# design.net
KiCad netlist of a schematic drawn in EAGLE
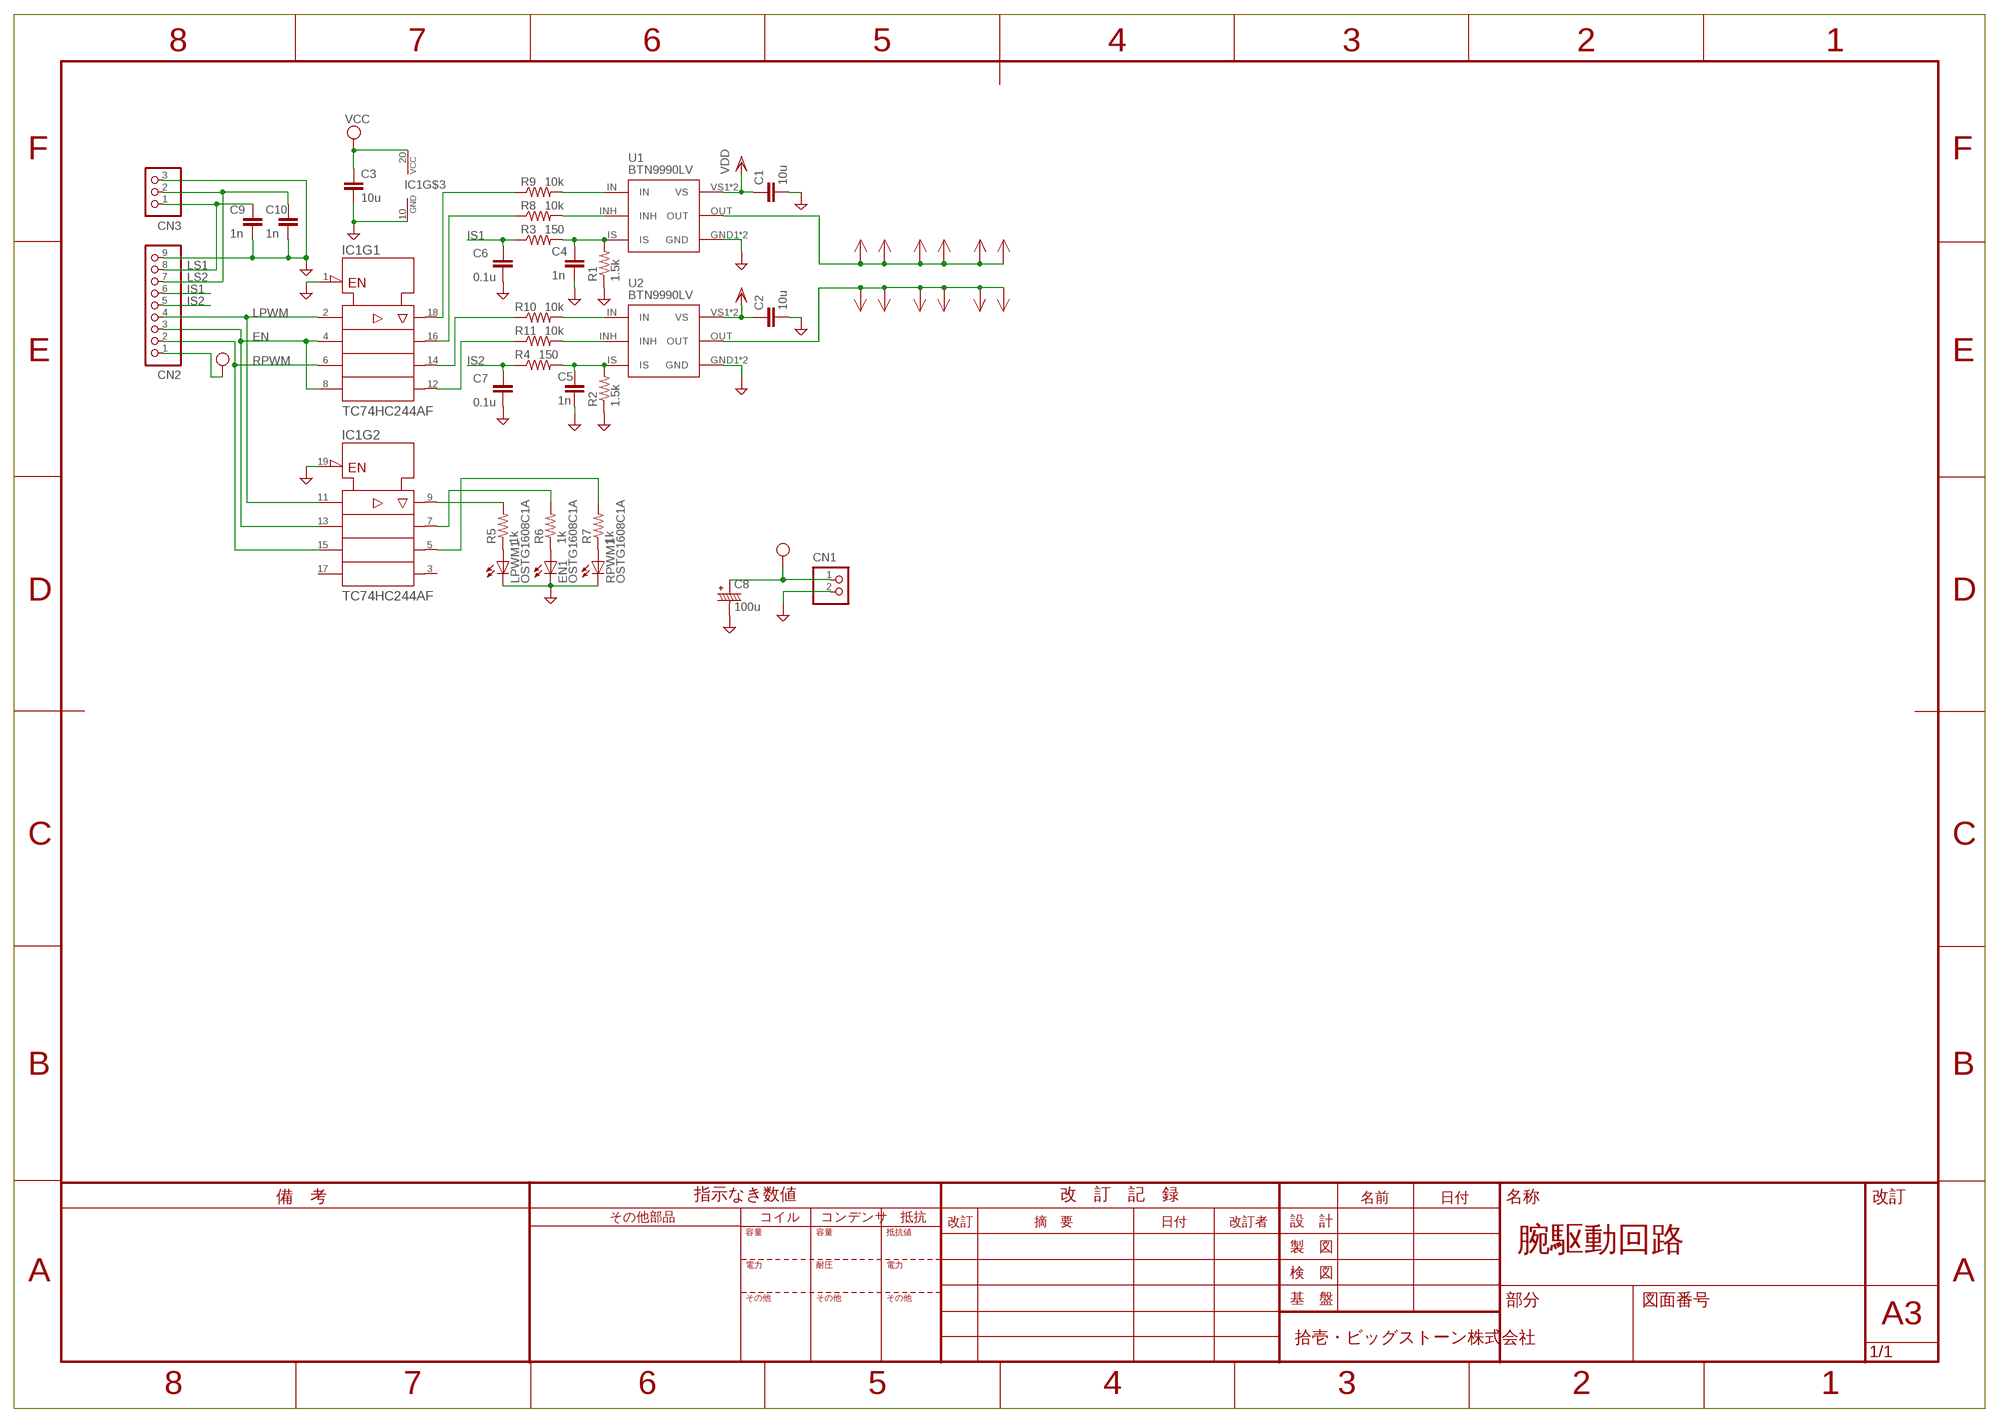
[diagram p0: schematic, sheet 1]

(export (version "E")
  (design (tool "Eeschema 10.0.6"))
  (components
    (comp (ref "C1")
      (value "10u")
      (footprint "eagle-import:C3216")
      (libsource (lib "eagle-import") (part "GCM?31CD71H106KE36K"))
    )
    (comp (ref "C2")
      (value "10u")
      (footprint "eagle-import:C3216")
      (libsource (lib "eagle-import") (part "GCM?31CD71H106KE36K"))
    )
    (comp (ref "C3")
      (value "10u")
      (footprint "eagle-import:C3216")
      (libsource (lib "eagle-import") (part "GCM?31CD71H106KE36K"))
    )
    (comp (ref "C4")
      (value "1n")
      (footprint "eagle-import:C1608")
      (libsource (lib "eagle-import") (part "GCM?188R91H102KA37D"))
    )
    (comp (ref "C5")
      (value "1n")
      (footprint "eagle-import:C1608")
      (libsource (lib "eagle-import") (part "GCM?188R91H102KA37D"))
    )
    (comp (ref "C6")
      (value "0.1u")
      (footprint "eagle-import:C1608")
      (libsource (lib "eagle-import") (part "GCM?188L81H104KA57D"))
    )
    (comp (ref "C7")
      (value "0.1u")
      (footprint "eagle-import:C1608")
      (libsource (lib "eagle-import") (part "GCM?188L81H104KA57D"))
    )
    (comp (ref "C8")
      (value "100u")
      (footprint "eagle-import:CPOL6.3-7_2.5")
      (libsource (lib "eagle-import") (part "16MH7100MEFC6.3X7"))
    )
    (comp (ref "C9")
      (value "1n")
      (footprint "eagle-import:C1608")
      (libsource (lib "eagle-import") (part "GCM?188R91H102KA37D"))
    )
    (comp (ref "C10")
      (value "1n")
      (footprint "eagle-import:C1608")
      (libsource (lib "eagle-import") (part "GCM?188R91H102KA37D"))
    )
    (comp (ref "CN1")
      (value "B2B-XH-A")
      (footprint "eagle-import:B2B-XH-A")
      (libsource (lib "eagle-import") (part "B2B-XH-A"))
    )
    (comp (ref "CN2")
      (value "B9B-XH-A")
      (footprint "eagle-import:B9B-XH-A")
      (libsource (lib "eagle-import") (part "B9B-XH-A"))
    )
    (comp (ref "CN3")
      (value "B3B-XH-A")
      (footprint "eagle-import:B3B-XH-A")
      (libsource (lib "eagle-import") (part "B3B-XH-A"))
    )
    (comp (ref "EN1")
      (value "OSTG1608C1A")
      (footprint "eagle-import:LEDC1608X39N_G")
      (libsource (lib "eagle-import") (part "OSTG1608C1A"))
    )
    (comp (ref "IC1")
      (value "TC74HC244AF")
      (footprint "eagle-import:SOP20")
      (libsource (lib "eagle-import") (part "TC74HC244AF"))
    )
    (comp (ref "LPWM1")
      (value "OSTG1608C1A")
      (footprint "eagle-import:LEDC1608X39N_G")
      (libsource (lib "eagle-import") (part "OSTG1608C1A"))
    )
    (comp (ref "OUT1")
      (value "VIA_2.5X5.25_D0.75")
      (footprint "eagle-import:VIA_2X5.25_D0.75")
      (libsource (lib "eagle-import") (part "VIA_2.5X5.25_D0.75"))
    )
    (comp (ref "R1")
      (value "1.5k")
      (footprint "eagle-import:R0603")
      (libsource (lib "eagle-import") (part "R1608"))
    )
    (comp (ref "R2")
      (value "1.5k")
      (footprint "eagle-import:R0603")
      (libsource (lib "eagle-import") (part "R1608"))
    )
    (comp (ref "R3")
      (value "150")
      (footprint "eagle-import:R0603")
      (libsource (lib "eagle-import") (part "R1608"))
    )
    (comp (ref "R4")
      (value "150")
      (footprint "eagle-import:R0603")
      (libsource (lib "eagle-import") (part "R1608"))
    )
    (comp (ref "R5")
      (value "1k")
      (footprint "eagle-import:R0603")
      (libsource (lib "eagle-import") (part "R1608"))
    )
    (comp (ref "R6")
      (value "1k")
      (footprint "eagle-import:R0603")
      (libsource (lib "eagle-import") (part "R1608"))
    )
    (comp (ref "R7")
      (value "1k")
      (footprint "eagle-import:R0603")
      (libsource (lib "eagle-import") (part "R1608"))
    )
    (comp (ref "R8")
      (value "10k")
      (footprint "eagle-import:R1608")
      (libsource (lib "eagle-import") (part "RC0603J10K"))
    )
    (comp (ref "R9")
      (value "10k")
      (footprint "eagle-import:R1608")
      (libsource (lib "eagle-import") (part "RC0603J10K"))
    )
    (comp (ref "R10")
      (value "10k")
      (footprint "eagle-import:R1608")
      (libsource (lib "eagle-import") (part "RC0603J10K"))
    )
    (comp (ref "R11")
      (value "10k")
      (footprint "eagle-import:R1608")
      (libsource (lib "eagle-import") (part "RC0603J10K"))
    )
    (comp (ref "RPWM1")
      (value "OSTG1608C1A")
      (footprint "eagle-import:LEDC1608X39N_G")
      (libsource (lib "eagle-import") (part "OSTG1608C1A"))
    )
    (comp (ref "U$2")
      (value "VIA_2.5X5.25_D0.75")
      (footprint "eagle-import:VIA_2X5.25_D0.75")
      (libsource (lib "eagle-import") (part "VIA_2.5X5.25_D0.75"))
    )
    (comp (ref "U$4")
      (value "VIA_2.5X5.25_D0.75")
      (footprint "eagle-import:VIA_2X5.25_D0.75")
      (libsource (lib "eagle-import") (part "VIA_2.5X5.25_D0.75"))
    )
    (comp (ref "U$5")
      (value "VIA_2.5X5.25_D0.75")
      (footprint "eagle-import:VIA_2X5.25_D0.75")
      (libsource (lib "eagle-import") (part "VIA_2.5X5.25_D0.75"))
    )
    (comp (ref "U$6")
      (value "VIA_2.5X5.25_D0.75")
      (footprint "eagle-import:VIA_2X5.25_D0.75")
      (libsource (lib "eagle-import") (part "VIA_2.5X5.25_D0.75"))
    )
    (comp (ref "U$7")
      (value "VIA_2.5X5.25_D0.75")
      (footprint "eagle-import:VIA_2X5.25_D0.75")
      (libsource (lib "eagle-import") (part "VIA_2.5X5.25_D0.75"))
    )
    (comp (ref "U$8")
      (value "VIA_2.5X5.25_D0.75")
      (footprint "eagle-import:VIA_2X5.25_D0.75")
      (libsource (lib "eagle-import") (part "VIA_2.5X5.25_D0.75"))
    )
    (comp (ref "U$9")
      (value "VIA_2.5X5.25_D0.75")
      (footprint "eagle-import:VIA_2X5.25_D0.75")
      (libsource (lib "eagle-import") (part "VIA_2.5X5.25_D0.75"))
    )
    (comp (ref "U$10")
      (value "VIA_2.5X5.25_D0.75")
      (footprint "eagle-import:VIA_2X5.25_D0.75")
      (libsource (lib "eagle-import") (part "VIA_2.5X5.25_D0.75"))
    )
    (comp (ref "U$11")
      (value "VIA_2.5X5.25_D0.75")
      (footprint "eagle-import:VIA_2X5.25_D0.75")
      (libsource (lib "eagle-import") (part "VIA_2.5X5.25_D0.75"))
    )
    (comp (ref "U$12")
      (value "VIA_2.5X5.25_D0.75")
      (footprint "eagle-import:VIA_2X5.25_D0.75")
      (libsource (lib "eagle-import") (part "VIA_2.5X5.25_D0.75"))
    )
    (comp (ref "U$13")
      (value "VIA_2.5X5.25_D0.75")
      (footprint "eagle-import:VIA_2X5.25_D0.75")
      (libsource (lib "eagle-import") (part "VIA_2.5X5.25_D0.75"))
    )
    (comp (ref "U1")
      (value "BTN9990LV")
      (footprint "eagle-import:BTN9990LV")
      (libsource (lib "eagle-import") (part "BTN9990LV"))
    )
    (comp (ref "U2")
      (value "BTN9990LV")
      (footprint "eagle-import:BTN9990LV")
      (libsource (lib "eagle-import") (part "BTN9990LV"))
    )
  )
  (nets
    (net (code "1") (name "/EN") (class "Default")
      (node (ref "CN2") (pin "3") (pinfunction "3_3") (pintype "passive"))
      (node (ref "IC1") (pin "13") (pinfunction "A2_13") (pintype "input"))
      (node (ref "IC1") (pin "4") (pinfunction "A2_4") (pintype "input"))
      (node (ref "IC1") (pin "8") (pinfunction "A4_8") (pintype "input"))
    )
    (net (code "2") (name "/IS1") (class "Default")
      (node (ref "C6") (pin "1") (pinfunction "1_1") (pintype "passive"))
      (node (ref "CN2") (pin "6") (pinfunction "6_6") (pintype "passive"))
      (node (ref "R3") (pin "1") (pinfunction "1_1") (pintype "passive"))
    )
    (net (code "3") (name "/IS2") (class "Default")
      (node (ref "C7") (pin "1") (pinfunction "1_1") (pintype "passive"))
      (node (ref "CN2") (pin "5") (pinfunction "5_5") (pintype "passive"))
      (node (ref "R4") (pin "1") (pinfunction "1_1") (pintype "passive"))
    )
    (net (code "4") (name "/LPWM") (class "Default")
      (node (ref "CN2") (pin "4") (pinfunction "4_4") (pintype "passive"))
      (node (ref "IC1") (pin "11") (pinfunction "A1_11") (pintype "input"))
      (node (ref "IC1") (pin "2") (pinfunction "A1_2") (pintype "input"))
    )
    (net (code "5") (name "/LS1") (class "Default")
      (node (ref "C9") (pin "1") (pinfunction "1_1") (pintype "passive"))
      (node (ref "CN2") (pin "8") (pinfunction "8_8") (pintype "passive"))
      (node (ref "CN3") (pin "1") (pinfunction "1_1") (pintype "passive"))
    )
    (net (code "6") (name "/LS2") (class "Default")
      (node (ref "C10") (pin "1") (pinfunction "1_1") (pintype "passive"))
      (node (ref "CN2") (pin "7") (pinfunction "7_7") (pintype "passive"))
      (node (ref "CN3") (pin "2") (pinfunction "2_2") (pintype "passive"))
    )
    (net (code "7") (name "/RPWM") (class "Default")
      (node (ref "CN2") (pin "2") (pinfunction "2_2") (pintype "passive"))
      (node (ref "IC1") (pin "15") (pinfunction "A3_15") (pintype "input"))
      (node (ref "IC1") (pin "6") (pinfunction "A3_6") (pintype "input"))
    )
    (net (code "8") (name "GND") (class "Default")
      (node (ref "C1") (pin "2") (pinfunction "2_2") (pintype "passive"))
      (node (ref "C10") (pin "2") (pinfunction "2_2") (pintype "passive"))
      (node (ref "C2") (pin "2") (pinfunction "2_2") (pintype "passive"))
      (node (ref "C3") (pin "2") (pinfunction "2_2") (pintype "passive"))
      (node (ref "C4") (pin "2") (pinfunction "2_2") (pintype "passive"))
      (node (ref "C5") (pin "2") (pinfunction "2_2") (pintype "passive"))
      (node (ref "C6") (pin "2") (pinfunction "2_2") (pintype "passive"))
      (node (ref "C7") (pin "2") (pinfunction "2_2") (pintype "passive"))
      (node (ref "C8") (pin "-") (pinfunction "-_-") (pintype "passive"))
      (node (ref "C9") (pin "2") (pinfunction "2_2") (pintype "passive"))
      (node (ref "CN1") (pin "2") (pinfunction "2_2") (pintype "passive"))
      (node (ref "CN2") (pin "9") (pinfunction "9_9") (pintype "passive"))
      (node (ref "CN3") (pin "3") (pinfunction "3_3") (pintype "passive"))
      (node (ref "EN1") (pin "K") (pinfunction "C_K") (pintype "passive"))
      (node (ref "IC1") (pin "1") (pinfunction "~{G}_1") (pintype "input"))
      (node (ref "IC1") (pin "10") (pinfunction "GND_10") (pintype "power_in"))
      (node (ref "IC1") (pin "19") (pinfunction "~{G}_19") (pintype "input"))
      (node (ref "LPWM1") (pin "K") (pinfunction "C_K") (pintype "passive"))
      (node (ref "R1") (pin "1") (pinfunction "1_1") (pintype "passive"))
      (node (ref "R2") (pin "1") (pinfunction "1_1") (pintype "passive"))
      (node (ref "RPWM1") (pin "K") (pinfunction "C_K") (pintype "passive"))
      (node (ref "U1") (pin "GND1") (pinfunction "GND_GND1") (pintype "bidirectional"))
      (node (ref "U1") (pin "GND2") (pinfunction "GND_GND2") (pintype "bidirectional"))
      (node (ref "U2") (pin "GND1") (pinfunction "GND_GND1") (pintype "bidirectional"))
      (node (ref "U2") (pin "GND2") (pinfunction "GND_GND2") (pintype "bidirectional"))
    )
    (net (code "9") (name "Net-(C4-Pad1)") (class "Default")
      (node (ref "C4") (pin "1") (pinfunction "1_1") (pintype "passive"))
      (node (ref "R1") (pin "2") (pinfunction "2_2") (pintype "passive"))
      (node (ref "R3") (pin "2") (pinfunction "2_2") (pintype "passive"))
      (node (ref "U1") (pin "IS") (pinfunction "IS_IS") (pintype "bidirectional"))
    )
    (net (code "10") (name "Net-(C5-Pad1)") (class "Default")
      (node (ref "C5") (pin "1") (pinfunction "1_1") (pintype "passive"))
      (node (ref "R2") (pin "2") (pinfunction "2_2") (pintype "passive"))
      (node (ref "R4") (pin "2") (pinfunction "2_2") (pintype "passive"))
      (node (ref "U2") (pin "IS") (pinfunction "IS_IS") (pintype "bidirectional"))
    )
    (net (code "11") (name "Net-(EN1-PadA)") (class "Default")
      (node (ref "EN1") (pin "A") (pinfunction "A_A") (pintype "passive"))
      (node (ref "R6") (pin "1") (pinfunction "1_1") (pintype "passive"))
    )
    (net (code "12") (name "Net-(IC1B-Y1)") (class "Default")
      (node (ref "IC1") (pin "18") (pinfunction "Y1_18") (pintype "tri_state"))
      (node (ref "R9") (pin "1") (pinfunction "1_1") (pintype "passive"))
    )
    (net (code "13") (name "Net-(IC1B-Y2)") (class "Default")
      (node (ref "IC1") (pin "16") (pinfunction "Y2_16") (pintype "tri_state"))
      (node (ref "R8") (pin "1") (pinfunction "1_1") (pintype "passive"))
    )
    (net (code "14") (name "Net-(IC1B-Y3)") (class "Default")
      (node (ref "IC1") (pin "14") (pinfunction "Y3_14") (pintype "tri_state"))
      (node (ref "R10") (pin "1") (pinfunction "1_1") (pintype "passive"))
    )
    (net (code "15") (name "Net-(IC1B-Y4)") (class "Default")
      (node (ref "IC1") (pin "12") (pinfunction "Y4_12") (pintype "tri_state"))
      (node (ref "R11") (pin "1") (pinfunction "1_1") (pintype "passive"))
    )
    (net (code "16") (name "Net-(IC1C-Y1)") (class "Default")
      (node (ref "IC1") (pin "9") (pinfunction "Y1_9") (pintype "tri_state"))
      (node (ref "R5") (pin "2") (pinfunction "2_2") (pintype "passive"))
    )
    (net (code "17") (name "Net-(IC1C-Y2)") (class "Default")
      (node (ref "IC1") (pin "7") (pinfunction "Y2_7") (pintype "tri_state"))
      (node (ref "R6") (pin "2") (pinfunction "2_2") (pintype "passive"))
    )
    (net (code "18") (name "Net-(IC1C-Y3)") (class "Default")
      (node (ref "IC1") (pin "5") (pinfunction "Y3_5") (pintype "tri_state"))
      (node (ref "R7") (pin "2") (pinfunction "2_2") (pintype "passive"))
    )
    (net (code "19") (name "Net-(LPWM1-PadA)") (class "Default")
      (node (ref "LPWM1") (pin "A") (pinfunction "A_A") (pintype "passive"))
      (node (ref "R5") (pin "1") (pinfunction "1_1") (pintype "passive"))
    )
    (net (code "20") (name "Net-(OUT1-PadP$1)") (class "Default")
      (node (ref "OUT1") (pin "P$1") (pinfunction "P$1_P$1") (pintype "bidirectional"))
      (node (ref "U$2") (pin "P$1") (pinfunction "P$1_P$1") (pintype "bidirectional"))
      (node (ref "U$4") (pin "P$1") (pinfunction "P$1_P$1") (pintype "bidirectional"))
      (node (ref "U$5") (pin "P$1") (pinfunction "P$1_P$1") (pintype "bidirectional"))
      (node (ref "U$6") (pin "P$1") (pinfunction "P$1_P$1") (pintype "bidirectional"))
      (node (ref "U$7") (pin "P$1") (pinfunction "P$1_P$1") (pintype "bidirectional"))
      (node (ref "U1") (pin "OUT") (pinfunction "OUT_OUT") (pintype "bidirectional"))
    )
    (net (code "21") (name "Net-(R7-Pad1)") (class "Default")
      (node (ref "R7") (pin "1") (pinfunction "1_1") (pintype "passive"))
      (node (ref "RPWM1") (pin "A") (pinfunction "A_A") (pintype "passive"))
    )
    (net (code "22") (name "Net-(R8-Pad2)") (class "Default")
      (node (ref "R8") (pin "2") (pinfunction "2_2") (pintype "passive"))
      (node (ref "U1") (pin "INH") (pinfunction "INH_INH") (pintype "bidirectional"))
    )
    (net (code "23") (name "Net-(R9-Pad2)") (class "Default")
      (node (ref "R9") (pin "2") (pinfunction "2_2") (pintype "passive"))
      (node (ref "U1") (pin "IN") (pinfunction "IN_IN") (pintype "bidirectional"))
    )
    (net (code "24") (name "Net-(R10-Pad2)") (class "Default")
      (node (ref "R10") (pin "2") (pinfunction "2_2") (pintype "passive"))
      (node (ref "U2") (pin "IN") (pinfunction "IN_IN") (pintype "bidirectional"))
    )
    (net (code "25") (name "Net-(R11-Pad2)") (class "Default")
      (node (ref "R11") (pin "2") (pinfunction "2_2") (pintype "passive"))
      (node (ref "U2") (pin "INH") (pinfunction "INH_INH") (pintype "bidirectional"))
    )
    (net (code "26") (name "Net-(U$10-PadP$1)") (class "Default")
      (node (ref "U$10") (pin "P$1") (pinfunction "P$1_P$1") (pintype "bidirectional"))
      (node (ref "U$11") (pin "P$1") (pinfunction "P$1_P$1") (pintype "bidirectional"))
      (node (ref "U$12") (pin "P$1") (pinfunction "P$1_P$1") (pintype "bidirectional"))
      (node (ref "U$13") (pin "P$1") (pinfunction "P$1_P$1") (pintype "bidirectional"))
      (node (ref "U$8") (pin "P$1") (pinfunction "P$1_P$1") (pintype "bidirectional"))
      (node (ref "U$9") (pin "P$1") (pinfunction "P$1_P$1") (pintype "bidirectional"))
      (node (ref "U2") (pin "OUT") (pinfunction "OUT_OUT") (pintype "bidirectional"))
    )
    (net (code "27") (name "VCC") (class "Default")
      (node (ref "C3") (pin "1") (pinfunction "1_1") (pintype "passive"))
      (node (ref "C8") (pin "+") (pinfunction "+_+") (pintype "passive"))
      (node (ref "CN1") (pin "1") (pinfunction "1_1") (pintype "passive"))
      (node (ref "CN2") (pin "1") (pinfunction "1_1") (pintype "passive"))
      (node (ref "IC1") (pin "20") (pinfunction "VCC_20") (pintype "power_in"))
    )
    (net (code "28") (name "VDD") (class "Default")
      (node (ref "C1") (pin "1") (pinfunction "1_1") (pintype "passive"))
      (node (ref "C2") (pin "1") (pinfunction "1_1") (pintype "passive"))
      (node (ref "U1") (pin "VS1") (pinfunction "VS_VS1") (pintype "bidirectional"))
      (node (ref "U1") (pin "VS2") (pinfunction "VS_VS2") (pintype "bidirectional"))
      (node (ref "U2") (pin "VS1") (pinfunction "VS_VS1") (pintype "bidirectional"))
      (node (ref "U2") (pin "VS2") (pinfunction "VS_VS2") (pintype "bidirectional"))
    )
    (net (code "29") (name "unconnected-(IC1C-A4-Pad17)") (class "Default")
      (node (ref "IC1") (pin "17") (pinfunction "A4_17") (pintype "input"))
    )
    (net (code "30") (name "unconnected-(IC1C-Y4-Pad3)") (class "Default")
      (node (ref "IC1") (pin "3") (pinfunction "Y4_3") (pintype "tri_state"))
    )
  )
)
